# 15P1D_EDA.net
KiCad netlist of a schematic drawn in EasyEDA Pro
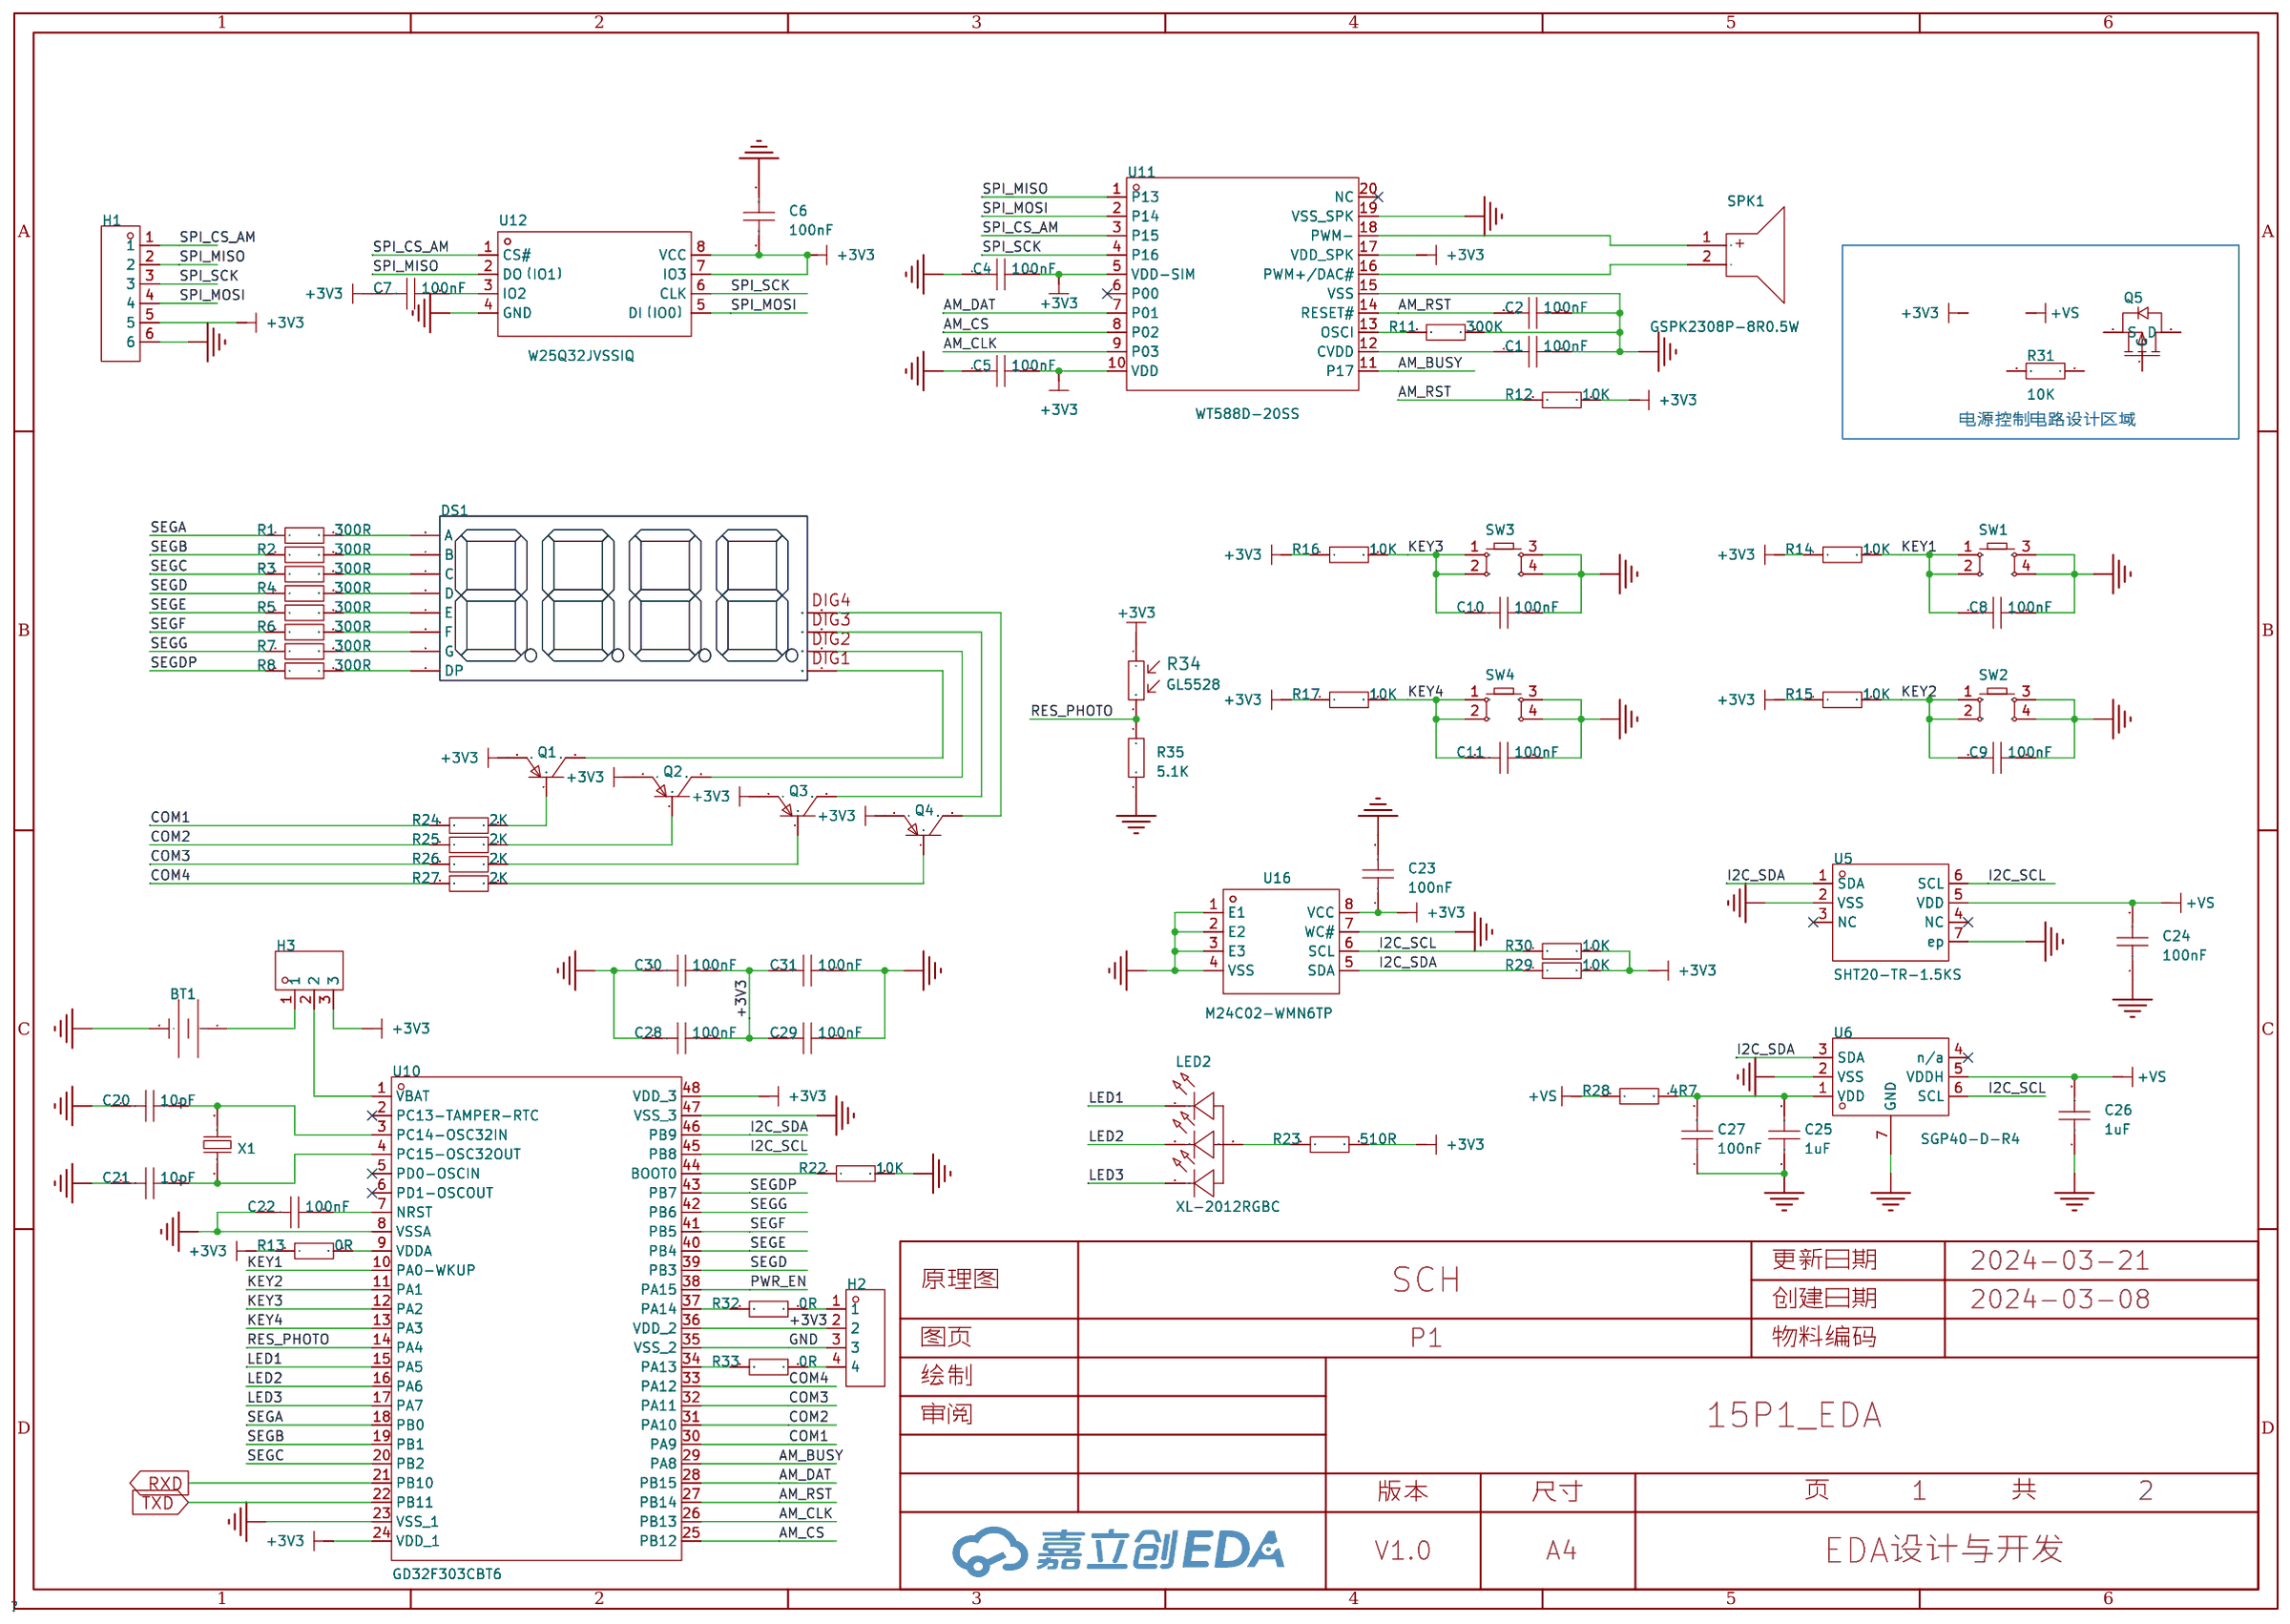
[diagram p0: P1]
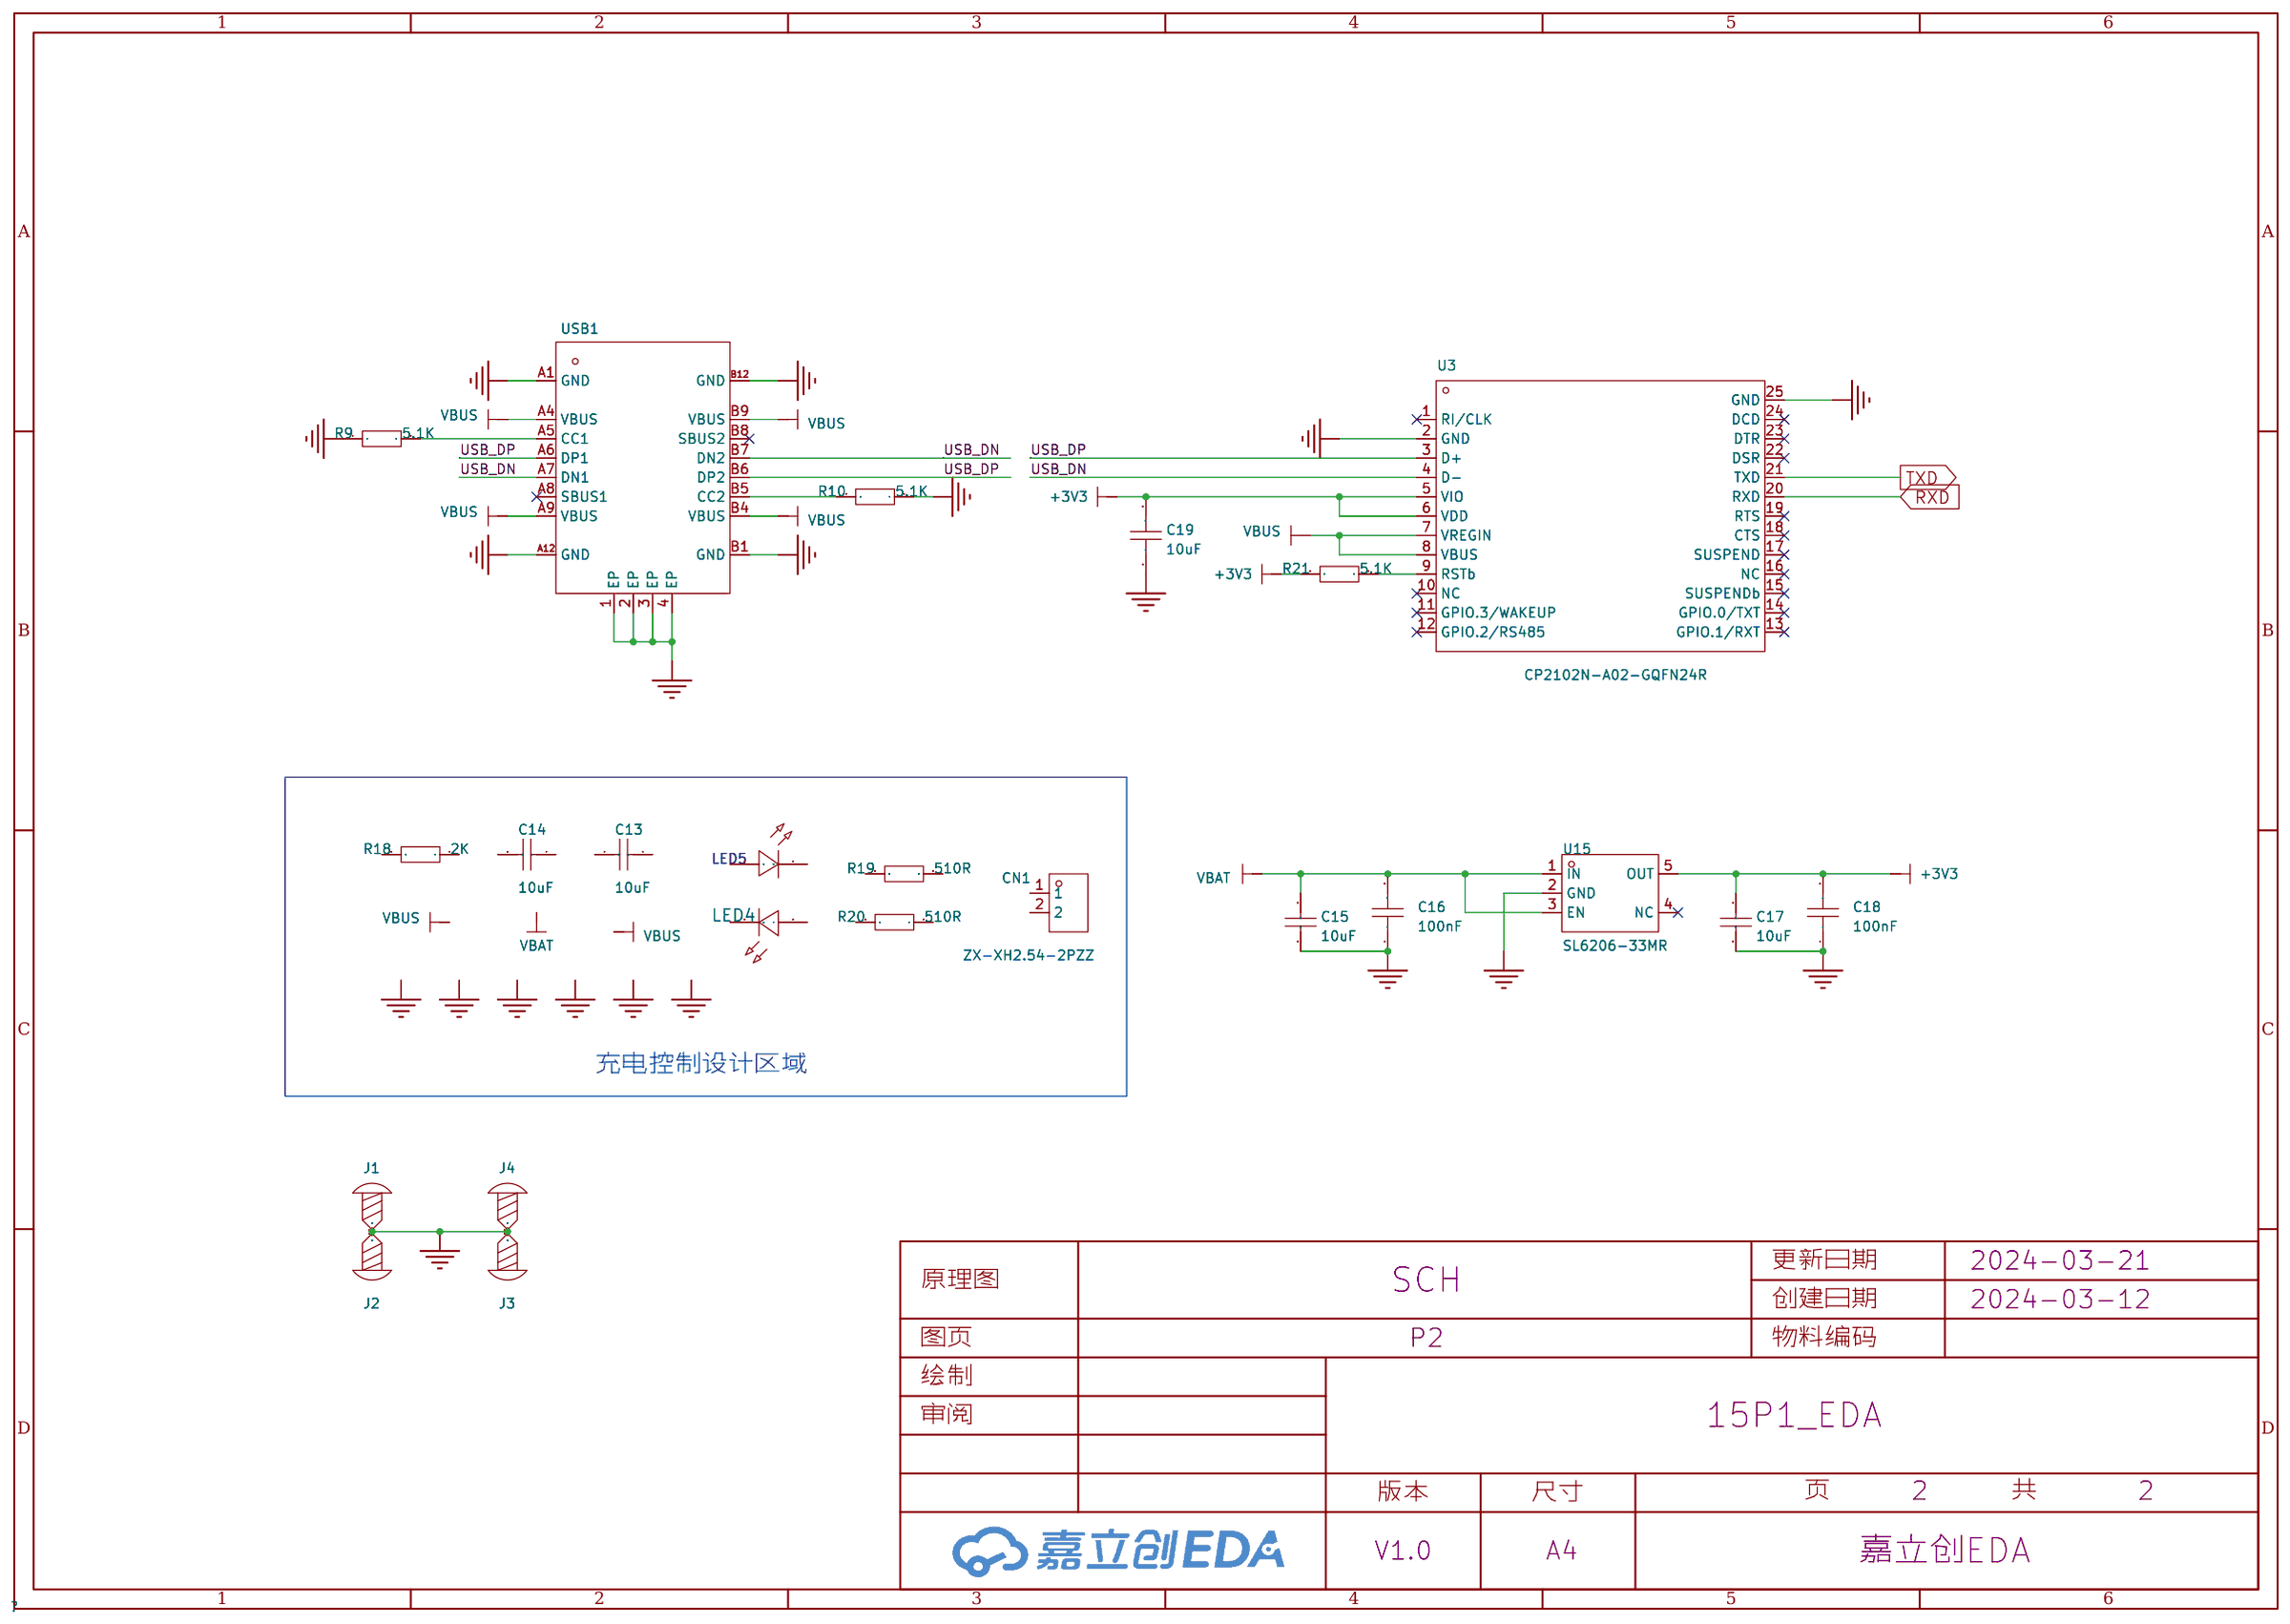
[diagram p1: P2]

(export (version "E")
  (design (tool "Eeschema 10.0.6"))
  (components
    (comp (ref "BT1")
      (value "BS-12-B3AA003")
      (footprint "easyedapro:BAT-SMD_BS-12-B3AA011")
      (description "连接器类型:电池底座;适用电池规格:CR1220;工作温度范围:-25°C~+85°C;")
      (fields (field (name "Manufacturer") "MYOUNG(美阳)"))
      (libsource (lib "easyedapro") (part "BS-12-B3AA003"))
    )
    (comp (ref "C1")
      (value "100nF")
      (footprint "easyedapro:C0805")
      (libsource (lib "easyedapro") (part "CapAcitance"))
    )
    (comp (ref "C2")
      (value "100nF")
      (footprint "easyedapro:C0805")
      (libsource (lib "easyedapro") (part "CapAcitance"))
    )
    (comp (ref "C4")
      (value "100nF")
      (footprint "easyedapro:C0805")
      (libsource (lib "easyedapro") (part "CapAcitance"))
    )
    (comp (ref "C5")
      (value "100nF")
      (footprint "easyedapro:C0805")
      (libsource (lib "easyedapro") (part "CapAcitance"))
    )
    (comp (ref "C6")
      (value "100nF")
      (footprint "easyedapro:C0805")
      (libsource (lib "easyedapro") (part "CapAcitance"))
    )
    (comp (ref "C7")
      (value "100nF")
      (footprint "easyedapro:C0805")
      (libsource (lib "easyedapro") (part "CapAcitance"))
    )
    (comp (ref "C8")
      (value "100nF")
      (footprint "easyedapro:C0805")
      (libsource (lib "easyedapro") (part "CapAcitance"))
    )
    (comp (ref "C9")
      (value "100nF")
      (footprint "easyedapro:C0805")
      (libsource (lib "easyedapro") (part "CapAcitance"))
    )
    (comp (ref "C10")
      (value "100nF")
      (footprint "easyedapro:C0805")
      (libsource (lib "easyedapro") (part "CapAcitance"))
    )
    (comp (ref "C11")
      (value "100nF")
      (footprint "easyedapro:C0805")
      (libsource (lib "easyedapro") (part "CapAcitance"))
    )
    (comp (ref "C20")
      (value "10pF")
      (footprint "easyedapro:C0805")
      (libsource (lib "easyedapro") (part "CapAcitance"))
    )
    (comp (ref "C21")
      (value "10pF")
      (footprint "easyedapro:C0805")
      (libsource (lib "easyedapro") (part "CapAcitance"))
    )
    (comp (ref "C22")
      (value "100nF")
      (footprint "easyedapro:C0805")
      (libsource (lib "easyedapro") (part "CapAcitance"))
    )
    (comp (ref "C23")
      (value "100nF")
      (footprint "easyedapro:C0805")
      (libsource (lib "easyedapro") (part "CapAcitance"))
    )
    (comp (ref "C24")
      (value "100nF")
      (footprint "easyedapro:C0805")
      (libsource (lib "easyedapro") (part "CapAcitance"))
    )
    (comp (ref "C25")
      (value "1uF")
      (footprint "easyedapro:C0805")
      (libsource (lib "easyedapro") (part "CapAcitance"))
    )
    (comp (ref "C26")
      (value "1uF")
      (footprint "easyedapro:C0805")
      (libsource (lib "easyedapro") (part "CapAcitance"))
    )
    (comp (ref "C27")
      (value "100nF")
      (footprint "easyedapro:C0805")
      (libsource (lib "easyedapro") (part "CapAcitance"))
    )
    (comp (ref "C28")
      (value "100nF")
      (footprint "easyedapro:C0805")
      (libsource (lib "easyedapro") (part "CapAcitance"))
    )
    (comp (ref "C29")
      (value "100nF")
      (footprint "easyedapro:C0805")
      (libsource (lib "easyedapro") (part "CapAcitance"))
    )
    (comp (ref "C30")
      (value "100nF")
      (footprint "easyedapro:C0805")
      (libsource (lib "easyedapro") (part "CapAcitance"))
    )
    (comp (ref "C31")
      (value "100nF")
      (footprint "easyedapro:C0805")
      (libsource (lib "easyedapro") (part "CapAcitance"))
    )
    (comp (ref "DS1")
      (value "~")
      (footprint "easyedapro:LED-SEG-TH_FJ5461AH")
      (libsource (lib "easyedapro") (part "LED_SEG_TH_0.56x4"))
    )
    (comp (ref "H1")
      (value "~")
      (footprint "easyedapro:HDR-TH_6P-P2.54-V-F")
      (libsource (lib "easyedapro") (part "Header-Female-2.54_1x6"))
    )
    (comp (ref "H2")
      (value "~")
      (footprint "easyedapro:HDR-TH_4P-P2.54-V-F")
      (libsource (lib "easyedapro") (part "2.54-1*4P母"))
    )
    (comp (ref "H3")
      (value "Jumper3")
      (footprint "easyedapro:HDR-TH_3P-P2.54-V-M-A")
      (libsource (lib "easyedapro") (part "JUMPER3"))
    )
    (comp (ref "LED2")
      (value "XL-2012RGBC")
      (footprint "easyedapro:LED-SMD_4P-L2.0-W1.3-BR")
      (fields (field (name "Manufacturer") "XINGLIGHT(成兴光)"))
      (libsource (lib "easyedapro") (part "XL-2012RGBC"))
    )
    (comp (ref "Q1")
      (value "~")
      (footprint "easyedapro:S8550P_SOT")
      (libsource (lib "easyedapro") (part "PNP"))
    )
    (comp (ref "Q2")
      (value "~")
      (footprint "easyedapro:S8550P_SOT")
      (libsource (lib "easyedapro") (part "PNP"))
    )
    (comp (ref "Q3")
      (value "~")
      (footprint "easyedapro:S8550P_SOT")
      (libsource (lib "easyedapro") (part "PNP"))
    )
    (comp (ref "Q4")
      (value "~")
      (footprint "easyedapro:S8550P_SOT")
      (libsource (lib "easyedapro") (part "PNP"))
    )
    (comp (ref "Q5")
      (value "~")
      (footprint "easyedapro:AO3401A_SOT-23-3")
      (libsource (lib "easyedapro") (part "P_MOS"))
    )
    (comp (ref "R1") (value "300R") (footprint "easyedapro:R0805") (libsource (lib "easyedapro") (part "电阻")))
    (comp (ref "R2") (value "300R") (footprint "easyedapro:R0805") (libsource (lib "easyedapro") (part "电阻")))
    (comp (ref "R3") (value "300R") (footprint "easyedapro:R0805") (libsource (lib "easyedapro") (part "电阻")))
    (comp (ref "R4") (value "300R") (footprint "easyedapro:R0805") (libsource (lib "easyedapro") (part "电阻")))
    (comp (ref "R5") (value "300R") (footprint "easyedapro:R0805") (libsource (lib "easyedapro") (part "电阻")))
    (comp (ref "R6") (value "300R") (footprint "easyedapro:R0805") (libsource (lib "easyedapro") (part "电阻")))
    (comp (ref "R7") (value "300R") (footprint "easyedapro:R0805") (libsource (lib "easyedapro") (part "电阻")))
    (comp (ref "R8") (value "300R") (footprint "easyedapro:R0805") (libsource (lib "easyedapro") (part "电阻")))
    (comp (ref "R11")
      (value "300K")
      (footprint "easyedapro:R0805")
      (libsource (lib "easyedapro") (part "电阻"))
    )
    (comp (ref "R12") (value "10K") (footprint "easyedapro:R0805") (libsource (lib "easyedapro") (part "电阻")))
    (comp (ref "R13") (value "0R") (footprint "easyedapro:R0805") (libsource (lib "easyedapro") (part "电阻")))
    (comp (ref "R14") (value "10K") (footprint "easyedapro:R0805") (libsource (lib "easyedapro") (part "电阻")))
    (comp (ref "R15") (value "10K") (footprint "easyedapro:R0805") (libsource (lib "easyedapro") (part "电阻")))
    (comp (ref "R16") (value "10K") (footprint "easyedapro:R0805") (libsource (lib "easyedapro") (part "电阻")))
    (comp (ref "R17") (value "10K") (footprint "easyedapro:R0805") (libsource (lib "easyedapro") (part "电阻")))
    (comp (ref "R22") (value "10K") (footprint "easyedapro:R0805") (libsource (lib "easyedapro") (part "电阻")))
    (comp (ref "R23")
      (value "510R")
      (footprint "easyedapro:R0805")
      (libsource (lib "easyedapro") (part "电阻"))
    )
    (comp (ref "R24") (value "2K") (footprint "easyedapro:R0805") (libsource (lib "easyedapro") (part "电阻")))
    (comp (ref "R25") (value "2K") (footprint "easyedapro:R0805") (libsource (lib "easyedapro") (part "电阻")))
    (comp (ref "R26") (value "2K") (footprint "easyedapro:R0805") (libsource (lib "easyedapro") (part "电阻")))
    (comp (ref "R27") (value "2K") (footprint "easyedapro:R0805") (libsource (lib "easyedapro") (part "电阻")))
    (comp (ref "R28") (value "4R7") (footprint "easyedapro:R0805") (libsource (lib "easyedapro") (part "电阻")))
    (comp (ref "R29") (value "10K") (footprint "easyedapro:R0805") (libsource (lib "easyedapro") (part "电阻")))
    (comp (ref "R30") (value "10K") (footprint "easyedapro:R0805") (libsource (lib "easyedapro") (part "电阻")))
    (comp (ref "R31") (value "10K") (footprint "easyedapro:R0805") (libsource (lib "easyedapro") (part "电阻")))
    (comp (ref "R32") (value "0R") (footprint "easyedapro:R0805") (libsource (lib "easyedapro") (part "电阻")))
    (comp (ref "R33") (value "0R") (footprint "easyedapro:R0805") (libsource (lib "easyedapro") (part "电阻")))
    (comp (ref "R34")
      (value "GL5528")
      (footprint "easyedapro:RES-TH_L5.1-W4.3-P3.40-D0.5")
      (description "暗电阻:1MΩ;亮电阻 @ 10Lux:8kΩ~20kΩ;光谱峰值(波长):540nm;")
      (fields (field (name "Manufacturer") "森霸"))
      (libsource (lib "easyedapro") (part "GL5528"))
    )
    (comp (ref "R35")
      (value "5.1K")
      (footprint "easyedapro:R0805")
      (libsource (lib "easyedapro") (part "电阻"))
    )
    (comp (ref "SPK1")
      (value "GSPK2308P-8R0.5W")
      (footprint "easyedapro:SPK-TH_BD23.0-P10.00-D0.8-L-RD")
      (fields (field (name "Manufacturer") "INGHAi(赢海)"))
      (libsource (lib "easyedapro") (part "GSPK2308P-8R0.5W"))
    )
    (comp (ref "SW1")
      (value "~")
      (footprint "easyedapro:Key_SMD_12x12x7.3")
      (libsource (lib "easyedapro") (part "轻触按键"))
    )
    (comp (ref "SW2")
      (value "~")
      (footprint "easyedapro:Key_SMD_12x12x7.3")
      (libsource (lib "easyedapro") (part "轻触按键"))
    )
    (comp (ref "SW3")
      (value "~")
      (footprint "easyedapro:Key_SMD_12x12x7.3")
      (libsource (lib "easyedapro") (part "轻触按键"))
    )
    (comp (ref "SW4")
      (value "~")
      (footprint "easyedapro:Key_SMD_12x12x7.3")
      (libsource (lib "easyedapro") (part "轻触按键"))
    )
    (comp (ref "U5")
      (value "SHT20-TR-1.5KS")
      (footprint "easyedapro:DFN-6_L3.0-W3.0-P0.95-TR-EP")
      (description "接口类型:I2C;")
      (fields (field (name "Manufacturer") "Sensirion(瑞士盛思锐)"))
      (libsource (lib "easyedapro") (part "SHT20"))
    )
    (comp (ref "U6")
      (value "SGP40-D-R4")
      (footprint "easyedapro:DFN-6_L2.4-W2.4-P0.80-TL-EP")
      (description "气体类型:空气质量;精度:-;")
      (fields (field (name "Manufacturer") "Sensirion(瑞士盛思锐)"))
      (libsource (lib "easyedapro") (part "SGP40-D-R4"))
    )
    (comp (ref "U10")
      (value "GD32F303CBT6")
      (footprint "easyedapro:LQFP-48_L7.0-W7.0-P0.50-LS9.0-BL")
      (description "CPU内核:CM4;程序存储容量:128KB;RAM总容量:32KB;GPIO端口数量:37;工作电压范围:-;CPU最大主频:120MHz;程序存储器类型:FLASH;")
      (fields (field (name "Manufacturer") "GigaDevice(兆易创新)"))
      (libsource (lib "easyedapro") (part "GD32F303CBT6"))
    )
    (comp (ref "U11")
      (value "WT588D-20SS")
      (footprint "easyedapro:SSOP-20_L7.2-W5.3-P0.65-LS7.8-BL")
      (description "高品质语音芯片")
      (fields (field (name "Manufacturer") "WT(唯创知音)"))
      (libsource (lib "easyedapro") (part "WT588D"))
    )
    (comp (ref "U12")
      (value "W25Q32JVSSIQ")
      (footprint "easyedapro:SOIC-8_L5.3-W5.3-P1.27-LS8.0-BL")
      (description "接口类型:SPI;存储容量:32Mbit;")
      (fields (field (name "Manufacturer") "WINBOND(华邦)"))
      (libsource (lib "easyedapro") (part "W25Q32JVSSIQ"))
    )
    (comp (ref "U16")
      (value "M24C02-WMN6TP")
      (footprint "easyedapro:SOIC-8_L4.9-W3.9-P1.27-LS6.0-BL")
      (description "接口类型:I2C;存储容量:2Kbit;")
      (fields (field (name "Manufacturer") "ST(意法半导体)"))
      (libsource (lib "easyedapro") (part "M24C02-WMN6TP"))
    )
    (comp (ref "X1")
      (value "32.768kHz")
      (footprint "easyedapro:FC-135R_L3.2-W1.5")
      (description "晶振类型:贴片晶振;频率:32.768kHz;常温频差:±20ppm;外接负载电容:12.5pF;")
      (fields (field (name "Manufacturer Part") "Q13FC13500004") (field (name "Manufacturer") "EPSON(爱普生)"))
      (libsource (lib "easyedapro") (part "Q13FC1350000400"))
    )
    (comp (ref "C13")
      (value "10uF")
      (footprint "easyedapro:C1206")
      (description "容值:10uF;精度:±10%;额定电压:50V;材质(温度系数):X5R;")
      (fields
        (field (name "Manufacturer Part") "CL31A106KBHNNNE")
        (field (name "Manufacturer") "SAMSUNG(三星)")
      )
      (libsource (lib "easyedapro") (part "CL31A106KBHNNNE"))
    )
    (comp (ref "C14")
      (value "10uF")
      (footprint "easyedapro:C1206")
      (description "容值:10uF;精度:±10%;额定电压:50V;材质(温度系数):X5R;")
      (fields
        (field (name "Manufacturer Part") "CL31A106KBHNNNE")
        (field (name "Manufacturer") "SAMSUNG(三星)")
      )
      (libsource (lib "easyedapro") (part "CL31A106KBHNNNE"))
    )
    (comp (ref "C15")
      (value "10uF")
      (footprint "easyedapro:C1206")
      (description "容值:10uF;精度:±10%;额定电压:50V;材质(温度系数):X5R;")
      (fields
        (field (name "Manufacturer Part") "CL31A106KBHNNNE")
        (field (name "Manufacturer") "SAMSUNG(三星)")
      )
      (libsource (lib "easyedapro") (part "CL31A106KBHNNNE"))
    )
    (comp (ref "C16")
      (value "100nF")
      (footprint "easyedapro:C0805")
      (libsource (lib "easyedapro") (part "CapAcitance"))
    )
    (comp (ref "C17")
      (value "10uF")
      (footprint "easyedapro:C1206")
      (description "容值:10uF;精度:±10%;额定电压:50V;材质(温度系数):X5R;")
      (fields
        (field (name "Manufacturer Part") "CL31A106KBHNNNE")
        (field (name "Manufacturer") "SAMSUNG(三星)")
      )
      (libsource (lib "easyedapro") (part "CL31A106KBHNNNE"))
    )
    (comp (ref "C18")
      (value "100nF")
      (footprint "easyedapro:C0805")
      (libsource (lib "easyedapro") (part "CapAcitance"))
    )
    (comp (ref "C19")
      (value "10uF")
      (footprint "easyedapro:C0805")
      (libsource (lib "easyedapro") (part "CapAcitance"))
    )
    (comp (ref "CN1")
      (value "ZX-XH2.54-2PZZ")
      (footprint "easyedapro:CONN-TH_2P-P2.50_HX25003-2A")
      (fields (field (name "Manufacturer") "Megastar(兆星)"))
      (libsource (lib "easyedapro") (part "ZX-XH2.54-2PZZ"))
    )
    (comp (ref "J1") (value "~") (footprint "easyedapro:M2螺丝") (libsource (lib "easyedapro") (part "螺丝孔")))
    (comp (ref "J2") (value "~") (footprint "easyedapro:M2螺丝") (libsource (lib "easyedapro") (part "螺丝孔")))
    (comp (ref "J3") (value "~") (footprint "easyedapro:M2螺丝") (libsource (lib "easyedapro") (part "螺丝孔")))
    (comp (ref "J4") (value "~") (footprint "easyedapro:M2螺丝") (libsource (lib "easyedapro") (part "螺丝孔")))
    (comp (ref "LED4")
      (value "~")
      (footprint "easyedapro:LED_0805")
      (libsource (lib "easyedapro") (part "LED_R"))
    )
    (comp (ref "LED5")
      (value "~")
      (footprint "easyedapro:LED_0805")
      (libsource (lib "easyedapro") (part "LED_G"))
    )
    (comp (ref "R9") (value "5.1K") (footprint "easyedapro:R0805") (libsource (lib "easyedapro") (part "电阻")))
    (comp (ref "R10")
      (value "5.1K")
      (footprint "easyedapro:R0805")
      (libsource (lib "easyedapro") (part "电阻"))
    )
    (comp (ref "R18") (value "2K") (footprint "easyedapro:R0805") (libsource (lib "easyedapro") (part "电阻")))
    (comp (ref "R19")
      (value "510R")
      (footprint "easyedapro:R0805")
      (libsource (lib "easyedapro") (part "电阻"))
    )
    (comp (ref "R20")
      (value "510R")
      (footprint "easyedapro:R0805")
      (libsource (lib "easyedapro") (part "电阻"))
    )
    (comp (ref "R21")
      (value "5.1K")
      (footprint "easyedapro:R0805")
      (libsource (lib "easyedapro") (part "电阻"))
    )
    (comp (ref "U3")
      (value "CP2102N-A02-GQFN24R")
      (footprint "easyedapro:QFN-24_L4.0-W4.0-P0.50-TL-EP2.6")
      (description "应用功能:USB转UART;接口协议:UART;")
      (fields (field (name "Manufacturer") "SKYWORKS/SILICON LABS(芯科)"))
      (libsource (lib "easyedapro") (part "CP2102N-A02-GQFN24R"))
    )
    (comp (ref "U15")
      (value "SL6206-33MR")
      (footprint "easyedapro:SOT-23-5_L2.9-W1.6-P0.95-LS2.8-BL")
      (description "输出类型:-;")
      (fields (field (name "Manufacturer") "Slkor(萨科微)"))
      (libsource (lib "easyedapro") (part "SL6206-33MR"))
    )
    (comp (ref "USB1")
      (value "~")
      (footprint "easyedapro:USB_TYPE-C-16P")
      (libsource (lib "easyedapro") (part "USB_TYPE-C-16P"))
    )
  )
  (nets
    (net (code "1") (name "+3V3") (class "Default")
      (node (ref "C17") (pin "2") (pinfunction "2_2") (pintype "input"))
      (node (ref "C18") (pin "2") (pinfunction "2_2") (pintype "input"))
      (node (ref "C19") (pin "2") (pinfunction "2_2") (pintype "input"))
      (node (ref "C23") (pin "1") (pinfunction "1_1") (pintype "input"))
      (node (ref "C28") (pin "1") (pinfunction "1_1") (pintype "input"))
      (node (ref "C29") (pin "2") (pinfunction "2_2") (pintype "input"))
      (node (ref "C30") (pin "1") (pinfunction "1_1") (pintype "input"))
      (node (ref "C31") (pin "2") (pinfunction "2_2") (pintype "input"))
      (node (ref "C4") (pin "2") (pinfunction "2_2") (pintype "input"))
      (node (ref "C5") (pin "2") (pinfunction "2_2") (pintype "input"))
      (node (ref "C6") (pin "2") (pinfunction "2_2") (pintype "input"))
      (node (ref "C7") (pin "1") (pinfunction "1_1") (pintype "input"))
      (node (ref "H1") (pin "5") (pinfunction "5_5") (pintype "unspecified"))
      (node (ref "H2") (pin "2") (pinfunction "2_2") (pintype "unspecified"))
      (node (ref "H3") (pin "3") (pinfunction "3_3") (pintype "input"))
      (node (ref "Q1") (pin "2") (pinfunction "E_2") (pintype "input"))
      (node (ref "Q2") (pin "2") (pinfunction "E_2") (pintype "input"))
      (node (ref "Q3") (pin "2") (pinfunction "E_2") (pintype "input"))
      (node (ref "Q4") (pin "2") (pinfunction "E_2") (pintype "input"))
      (node (ref "R12") (pin "2") (pinfunction "2_2") (pintype "input"))
      (node (ref "R13") (pin "1") (pinfunction "1_1") (pintype "input"))
      (node (ref "R14") (pin "1") (pinfunction "1_1") (pintype "input"))
      (node (ref "R15") (pin "1") (pinfunction "1_1") (pintype "input"))
      (node (ref "R16") (pin "1") (pinfunction "1_1") (pintype "input"))
      (node (ref "R17") (pin "1") (pinfunction "1_1") (pintype "input"))
      (node (ref "R21") (pin "2") (pinfunction "2_2") (pintype "input"))
      (node (ref "R23") (pin "2") (pinfunction "2_2") (pintype "input"))
      (node (ref "R29") (pin "2") (pinfunction "2_2") (pintype "input"))
      (node (ref "R30") (pin "2") (pinfunction "2_2") (pintype "input"))
      (node (ref "R34") (pin "1") (pinfunction "1_1") (pintype "input"))
      (node (ref "U10") (pin "24") (pinfunction "VDD_1_24") (pintype "unspecified"))
      (node (ref "U10") (pin "36") (pinfunction "VDD_2_36") (pintype "unspecified"))
      (node (ref "U10") (pin "48") (pinfunction "VDD_3_48") (pintype "unspecified"))
      (node (ref "U11") (pin "10") (pinfunction "VDD_10") (pintype "input"))
      (node (ref "U11") (pin "17") (pinfunction "VDD_SPK_17") (pintype "input"))
      (node (ref "U11") (pin "5") (pinfunction "VDD-SIM_5") (pintype "input"))
      (node (ref "U12") (pin "7") (pinfunction "IO3_7") (pintype "unspecified"))
      (node (ref "U12") (pin "8") (pinfunction "VCC_8") (pintype "unspecified"))
      (node (ref "U15") (pin "5") (pinfunction "OUT_5") (pintype "unspecified"))
      (node (ref "U16") (pin "8") (pinfunction "VCC_8") (pintype "unspecified"))
      (node (ref "U3") (pin "5") (pinfunction "VIO_5") (pintype "unspecified"))
      (node (ref "U3") (pin "6") (pinfunction "VDD_6") (pintype "unspecified"))
    )
    (net (code "2") (name "+VS") (class "Default")
      (node (ref "C24") (pin "2") (pinfunction "2_2") (pintype "input"))
      (node (ref "C26") (pin "2") (pinfunction "2_2") (pintype "input"))
      (node (ref "R28") (pin "1") (pinfunction "1_1") (pintype "input"))
      (node (ref "U5") (pin "5") (pinfunction "VDD_5") (pintype "unspecified"))
      (node (ref "U6") (pin "5") (pinfunction "VDDH_5") (pintype "unspecified"))
    )
    (net (code "3") (name "AM_BUSY") (class "Default")
      (node (ref "U10") (pin "29") (pinfunction "PA8_29") (pintype "unspecified"))
      (node (ref "U11") (pin "11") (pinfunction "P17_11") (pintype "input"))
    )
    (net (code "4") (name "AM_CLK") (class "Default")
      (node (ref "U10") (pin "26") (pinfunction "PB13_26") (pintype "unspecified"))
      (node (ref "U11") (pin "9") (pinfunction "P03_9") (pintype "input"))
    )
    (net (code "5") (name "AM_CS") (class "Default")
      (node (ref "U10") (pin "25") (pinfunction "PB12_25") (pintype "unspecified"))
      (node (ref "U11") (pin "8") (pinfunction "P02_8") (pintype "input"))
    )
    (net (code "6") (name "AM_DAT") (class "Default")
      (node (ref "U10") (pin "28") (pinfunction "PB15_28") (pintype "unspecified"))
      (node (ref "U11") (pin "7") (pinfunction "P01_7") (pintype "input"))
    )
    (net (code "7") (name "AM_RST") (class "Default")
      (node (ref "C2") (pin "1") (pinfunction "1_1") (pintype "input"))
      (node (ref "R12") (pin "1") (pinfunction "1_1") (pintype "input"))
      (node (ref "U10") (pin "27") (pinfunction "PB14_27") (pintype "unspecified"))
      (node (ref "U11") (pin "14") (pinfunction "RESET#_14") (pintype "input"))
    )
    (net (code "8") (name "COM1") (class "Default")
      (node (ref "R24") (pin "1") (pinfunction "1_1") (pintype "input"))
      (node (ref "U10") (pin "30") (pinfunction "PA9_30") (pintype "unspecified"))
    )
    (net (code "9") (name "COM2") (class "Default")
      (node (ref "R25") (pin "1") (pinfunction "1_1") (pintype "input"))
      (node (ref "U10") (pin "31") (pinfunction "PA10_31") (pintype "unspecified"))
    )
    (net (code "10") (name "COM3") (class "Default")
      (node (ref "R26") (pin "1") (pinfunction "1_1") (pintype "input"))
      (node (ref "U10") (pin "32") (pinfunction "PA11_32") (pintype "unspecified"))
    )
    (net (code "11") (name "COM4") (class "Default")
      (node (ref "R27") (pin "1") (pinfunction "1_1") (pintype "input"))
      (node (ref "U10") (pin "33") (pinfunction "PA12_33") (pintype "unspecified"))
    )
    (net (code "12") (name "GND") (class "Default")
      (node (ref "BT1") (pin "2") (pinfunction "-_2") (pintype "unspecified"))
      (node (ref "C1") (pin "2") (pinfunction "2_2") (pintype "input"))
      (node (ref "C10") (pin "2") (pinfunction "2_2") (pintype "input"))
      (node (ref "C11") (pin "2") (pinfunction "2_2") (pintype "input"))
      (node (ref "C15") (pin "1") (pinfunction "1_1") (pintype "input"))
      (node (ref "C16") (pin "1") (pinfunction "1_1") (pintype "input"))
      (node (ref "C17") (pin "1") (pinfunction "1_1") (pintype "input"))
      (node (ref "C18") (pin "1") (pinfunction "1_1") (pintype "input"))
      (node (ref "C19") (pin "1") (pinfunction "1_1") (pintype "input"))
      (node (ref "C2") (pin "2") (pinfunction "2_2") (pintype "input"))
      (node (ref "C20") (pin "1") (pinfunction "1_1") (pintype "input"))
      (node (ref "C21") (pin "1") (pinfunction "1_1") (pintype "input"))
      (node (ref "C22") (pin "1") (pinfunction "1_1") (pintype "input"))
      (node (ref "C23") (pin "2") (pinfunction "2_2") (pintype "input"))
      (node (ref "C24") (pin "1") (pinfunction "1_1") (pintype "input"))
      (node (ref "C25") (pin "1") (pinfunction "1_1") (pintype "input"))
      (node (ref "C26") (pin "1") (pinfunction "1_1") (pintype "input"))
      (node (ref "C27") (pin "1") (pinfunction "1_1") (pintype "input"))
      (node (ref "C28") (pin "2") (pinfunction "2_2") (pintype "input"))
      (node (ref "C29") (pin "1") (pinfunction "1_1") (pintype "input"))
      (node (ref "C30") (pin "2") (pinfunction "2_2") (pintype "input"))
      (node (ref "C31") (pin "1") (pinfunction "1_1") (pintype "input"))
      (node (ref "C4") (pin "1") (pinfunction "1_1") (pintype "input"))
      (node (ref "C5") (pin "1") (pinfunction "1_1") (pintype "input"))
      (node (ref "C6") (pin "1") (pinfunction "1_1") (pintype "input"))
      (node (ref "C8") (pin "2") (pinfunction "2_2") (pintype "input"))
      (node (ref "C9") (pin "2") (pinfunction "2_2") (pintype "input"))
      (node (ref "H1") (pin "6") (pinfunction "6_6") (pintype "unspecified"))
      (node (ref "H2") (pin "3") (pinfunction "3_3") (pintype "unspecified"))
      (node (ref "J1") (pin "1") (pinfunction "1_1") (pintype "input"))
      (node (ref "J2") (pin "1") (pinfunction "1_1") (pintype "input"))
      (node (ref "J3") (pin "1") (pinfunction "1_1") (pintype "input"))
      (node (ref "J4") (pin "1") (pinfunction "1_1") (pintype "input"))
      (node (ref "R10") (pin "1") (pinfunction "1_1") (pintype "input"))
      (node (ref "R11") (pin "2") (pinfunction "2_2") (pintype "input"))
      (node (ref "R22") (pin "2") (pinfunction "2_2") (pintype "input"))
      (node (ref "R35") (pin "2") (pinfunction "2_2") (pintype "input"))
      (node (ref "R9") (pin "1") (pinfunction "1_1") (pintype "input"))
      (node (ref "SW1") (pin "3") (pinfunction "3_3") (pintype "input"))
      (node (ref "SW1") (pin "4") (pinfunction "4_4") (pintype "input"))
      (node (ref "SW2") (pin "3") (pinfunction "3_3") (pintype "input"))
      (node (ref "SW2") (pin "4") (pinfunction "4_4") (pintype "input"))
      (node (ref "SW3") (pin "3") (pinfunction "3_3") (pintype "input"))
      (node (ref "SW3") (pin "4") (pinfunction "4_4") (pintype "input"))
      (node (ref "SW4") (pin "3") (pinfunction "3_3") (pintype "input"))
      (node (ref "SW4") (pin "4") (pinfunction "4_4") (pintype "input"))
      (node (ref "U10") (pin "23") (pinfunction "VSS_1_23") (pintype "unspecified"))
      (node (ref "U10") (pin "35") (pinfunction "VSS_2_35") (pintype "unspecified"))
      (node (ref "U10") (pin "47") (pinfunction "VSS_3_47") (pintype "unspecified"))
      (node (ref "U10") (pin "8") (pinfunction "VSSA_8") (pintype "unspecified"))
      (node (ref "U11") (pin "15") (pinfunction "VSS_15") (pintype "input"))
      (node (ref "U11") (pin "19") (pinfunction "VSS_SPK_19") (pintype "input"))
      (node (ref "U12") (pin "4") (pinfunction "GND_4") (pintype "unspecified"))
      (node (ref "U15") (pin "2") (pinfunction "GND_2") (pintype "unspecified"))
      (node (ref "U16") (pin "1") (pinfunction "E1_1") (pintype "unspecified"))
      (node (ref "U16") (pin "2") (pinfunction "E2_2") (pintype "unspecified"))
      (node (ref "U16") (pin "3") (pinfunction "E3_3") (pintype "unspecified"))
      (node (ref "U16") (pin "4") (pinfunction "VSS_4") (pintype "unspecified"))
      (node (ref "U16") (pin "7") (pinfunction "WC#_7") (pintype "unspecified"))
      (node (ref "U3") (pin "2") (pinfunction "GND_2") (pintype "unspecified"))
      (node (ref "U3") (pin "25") (pinfunction "GND_25") (pintype "unspecified"))
      (node (ref "U5") (pin "2") (pinfunction "VSS_2") (pintype "unspecified"))
      (node (ref "U5") (pin "7") (pinfunction "ep_7") (pintype "unspecified"))
      (node (ref "U6") (pin "2") (pinfunction "VSS_2") (pintype "unspecified"))
      (node (ref "U6") (pin "7") (pinfunction "GND_7") (pintype "unspecified"))
      (node (ref "USB1") (pin "1") (pinfunction "EP_1") (pintype "input"))
      (node (ref "USB1") (pin "2") (pinfunction "EP_2") (pintype "input"))
      (node (ref "USB1") (pin "3") (pinfunction "EP_3") (pintype "input"))
      (node (ref "USB1") (pin "4") (pinfunction "EP_4") (pintype "input"))
      (node (ref "USB1") (pin "A1") (pinfunction "GND_A1") (pintype "input"))
      (node (ref "USB1") (pin "A12") (pinfunction "GND_A12") (pintype "input"))
      (node (ref "USB1") (pin "B1") (pinfunction "GND_B1") (pintype "input"))
      (node (ref "USB1") (pin "B12") (pinfunction "GND_B12") (pintype "input"))
    )
    (net (code "13") (name "I2C_SCL") (class "Default")
      (node (ref "R30") (pin "1") (pinfunction "1_1") (pintype "input"))
      (node (ref "U10") (pin "45") (pinfunction "PB8_45") (pintype "unspecified"))
      (node (ref "U16") (pin "6") (pinfunction "SCL_6") (pintype "unspecified"))
      (node (ref "U5") (pin "6") (pinfunction "SCL_6") (pintype "unspecified"))
      (node (ref "U6") (pin "6") (pinfunction "SCL_6") (pintype "unspecified"))
    )
    (net (code "14") (name "I2C_SDA") (class "Default")
      (node (ref "R29") (pin "1") (pinfunction "1_1") (pintype "input"))
      (node (ref "U10") (pin "46") (pinfunction "PB9_46") (pintype "unspecified"))
      (node (ref "U16") (pin "5") (pinfunction "SDA_5") (pintype "unspecified"))
      (node (ref "U5") (pin "1") (pinfunction "SDA_1") (pintype "unspecified"))
      (node (ref "U6") (pin "3") (pinfunction "SDA_3") (pintype "unspecified"))
    )
    (net (code "15") (name "KEY1") (class "Default")
      (node (ref "C8") (pin "1") (pinfunction "1_1") (pintype "input"))
      (node (ref "R14") (pin "2") (pinfunction "2_2") (pintype "input"))
      (node (ref "SW1") (pin "1") (pinfunction "1_1") (pintype "input"))
      (node (ref "SW1") (pin "2") (pinfunction "2_2") (pintype "input"))
      (node (ref "U10") (pin "10") (pinfunction "PA0-WKUP_10") (pintype "unspecified"))
    )
    (net (code "16") (name "KEY2") (class "Default")
      (node (ref "C9") (pin "1") (pinfunction "1_1") (pintype "input"))
      (node (ref "R15") (pin "2") (pinfunction "2_2") (pintype "input"))
      (node (ref "SW2") (pin "1") (pinfunction "1_1") (pintype "input"))
      (node (ref "SW2") (pin "2") (pinfunction "2_2") (pintype "input"))
      (node (ref "U10") (pin "11") (pinfunction "PA1_11") (pintype "unspecified"))
    )
    (net (code "17") (name "KEY3") (class "Default")
      (node (ref "C10") (pin "1") (pinfunction "1_1") (pintype "input"))
      (node (ref "R16") (pin "2") (pinfunction "2_2") (pintype "input"))
      (node (ref "SW3") (pin "1") (pinfunction "1_1") (pintype "input"))
      (node (ref "SW3") (pin "2") (pinfunction "2_2") (pintype "input"))
      (node (ref "U10") (pin "12") (pinfunction "PA2_12") (pintype "unspecified"))
    )
    (net (code "18") (name "KEY4") (class "Default")
      (node (ref "C11") (pin "1") (pinfunction "1_1") (pintype "input"))
      (node (ref "R17") (pin "2") (pinfunction "2_2") (pintype "input"))
      (node (ref "SW4") (pin "1") (pinfunction "1_1") (pintype "input"))
      (node (ref "SW4") (pin "2") (pinfunction "2_2") (pintype "input"))
      (node (ref "U10") (pin "13") (pinfunction "PA3_13") (pintype "unspecified"))
    )
    (net (code "19") (name "LED1") (class "Default")
      (node (ref "LED2") (pin "1") (pinfunction "1_1") (pintype "unspecified"))
      (node (ref "U10") (pin "15") (pinfunction "PA5_15") (pintype "unspecified"))
    )
    (net (code "20") (name "LED2") (class "Default")
      (node (ref "LED2") (pin "2") (pinfunction "2_2") (pintype "unspecified"))
      (node (ref "U10") (pin "16") (pinfunction "PA6_16") (pintype "unspecified"))
    )
    (net (code "21") (name "LED3") (class "Default")
      (node (ref "LED2") (pin "4") (pinfunction "4_4") (pintype "unspecified"))
      (node (ref "U10") (pin "17") (pinfunction "PA7_17") (pintype "unspecified"))
    )
    (net (code "22") (name "Net-(BT1-+)") (class "Default")
      (node (ref "BT1") (pin "1") (pinfunction "+_1") (pintype "unspecified"))
      (node (ref "H3") (pin "1") (pinfunction "1_1") (pintype "input"))
    )
    (net (code "23") (name "Net-(DS1-A)") (class "Default")
      (node (ref "DS1") (pin "11") (pinfunction "A_11") (pintype "input"))
      (node (ref "R1") (pin "2") (pinfunction "2_2") (pintype "input"))
    )
    (net (code "24") (name "Net-(DS1-B)") (class "Default")
      (node (ref "DS1") (pin "7") (pinfunction "B_7") (pintype "input"))
      (node (ref "R2") (pin "2") (pinfunction "2_2") (pintype "input"))
    )
    (net (code "25") (name "Net-(DS1-C)") (class "Default")
      (node (ref "DS1") (pin "4") (pinfunction "C_4") (pintype "input"))
      (node (ref "R3") (pin "2") (pinfunction "2_2") (pintype "input"))
    )
    (net (code "26") (name "Net-(DS1-D)") (class "Default")
      (node (ref "DS1") (pin "2") (pinfunction "D_2") (pintype "input"))
      (node (ref "R4") (pin "2") (pinfunction "2_2") (pintype "input"))
    )
    (net (code "27") (name "Net-(DS1-DIG1)") (class "Default")
      (node (ref "DS1") (pin "12") (pinfunction "DIG1_12") (pintype "input"))
      (node (ref "Q1") (pin "3") (pinfunction "C_3") (pintype "input"))
    )
    (net (code "28") (name "Net-(DS1-DIG2)") (class "Default")
      (node (ref "DS1") (pin "9") (pinfunction "DIG2_9") (pintype "input"))
      (node (ref "Q2") (pin "3") (pinfunction "C_3") (pintype "input"))
    )
    (net (code "29") (name "Net-(DS1-DIG3)") (class "Default")
      (node (ref "DS1") (pin "8") (pinfunction "DIG3_8") (pintype "input"))
      (node (ref "Q3") (pin "3") (pinfunction "C_3") (pintype "input"))
    )
    (net (code "30") (name "Net-(DS1-DIG4)") (class "Default")
      (node (ref "DS1") (pin "6") (pinfunction "DIG4_6") (pintype "input"))
      (node (ref "Q4") (pin "3") (pinfunction "C_3") (pintype "input"))
    )
    (net (code "31") (name "Net-(DS1-DP)") (class "Default")
      (node (ref "DS1") (pin "3") (pinfunction "DP_3") (pintype "input"))
      (node (ref "R8") (pin "2") (pinfunction "2_2") (pintype "input"))
    )
    (net (code "32") (name "Net-(DS1-E)") (class "Default")
      (node (ref "DS1") (pin "1") (pinfunction "E_1") (pintype "input"))
      (node (ref "R5") (pin "2") (pinfunction "2_2") (pintype "input"))
    )
    (net (code "33") (name "Net-(DS1-F)") (class "Default")
      (node (ref "DS1") (pin "10") (pinfunction "F_10") (pintype "input"))
      (node (ref "R6") (pin "2") (pinfunction "2_2") (pintype "input"))
    )
    (net (code "34") (name "Net-(DS1-G)") (class "Default")
      (node (ref "DS1") (pin "5") (pinfunction "G_5") (pintype "input"))
      (node (ref "R7") (pin "2") (pinfunction "2_2") (pintype "input"))
    )
    (net (code "35") (name "Net-(H2-Pad1)") (class "Default")
      (node (ref "H2") (pin "1") (pinfunction "1_1") (pintype "unspecified"))
      (node (ref "R32") (pin "2") (pinfunction "2_2") (pintype "input"))
    )
    (net (code "36") (name "Net-(H2-Pad4)") (class "Default")
      (node (ref "H2") (pin "4") (pinfunction "4_4") (pintype "unspecified"))
      (node (ref "R33") (pin "2") (pinfunction "2_2") (pintype "input"))
    )
    (net (code "37") (name "Net-(LED2-Pad3)") (class "Default")
      (node (ref "LED2") (pin "3") (pinfunction "3_3") (pintype "unspecified"))
      (node (ref "R23") (pin "1") (pinfunction "1_1") (pintype "input"))
    )
    (net (code "38") (name "Net-(Q1-B)") (class "Default")
      (node (ref "Q1") (pin "1") (pinfunction "B_1") (pintype "input"))
      (node (ref "R24") (pin "2") (pinfunction "2_2") (pintype "input"))
    )
    (net (code "39") (name "Net-(Q2-B)") (class "Default")
      (node (ref "Q2") (pin "1") (pinfunction "B_1") (pintype "input"))
      (node (ref "R25") (pin "2") (pinfunction "2_2") (pintype "input"))
    )
    (net (code "40") (name "Net-(Q3-B)") (class "Default")
      (node (ref "Q3") (pin "1") (pinfunction "B_1") (pintype "input"))
      (node (ref "R26") (pin "2") (pinfunction "2_2") (pintype "input"))
    )
    (net (code "41") (name "Net-(Q4-B)") (class "Default")
      (node (ref "Q4") (pin "1") (pinfunction "B_1") (pintype "input"))
      (node (ref "R27") (pin "2") (pinfunction "2_2") (pintype "input"))
    )
    (net (code "42") (name "Net-(SPK1-+)") (class "Default")
      (node (ref "SPK1") (pin "1") (pinfunction "+_1") (pintype "input"))
      (node (ref "U11") (pin "18") (pinfunction "PWM-_18") (pintype "input"))
    )
    (net (code "43") (name "Net-(SPK1--)") (class "Default")
      (node (ref "SPK1") (pin "2") (pinfunction "-_2") (pintype "input"))
      (node (ref "U11") (pin "16") (pinfunction "PWM+/DAC#_16") (pintype "input"))
    )
    (net (code "44") (name "Net-(U3-RSTb)") (class "Default")
      (node (ref "R21") (pin "1") (pinfunction "1_1") (pintype "input"))
      (node (ref "U3") (pin "9") (pinfunction "RSTb_9") (pintype "unspecified"))
    )
    (net (code "45") (name "Net-(U6-VDD)") (class "Default")
      (node (ref "C25") (pin "2") (pinfunction "2_2") (pintype "input"))
      (node (ref "C27") (pin "2") (pinfunction "2_2") (pintype "input"))
      (node (ref "R28") (pin "2") (pinfunction "2_2") (pintype "input"))
      (node (ref "U6") (pin "1") (pinfunction "VDD_1") (pintype "unspecified"))
    )
    (net (code "46") (name "Net-(U10-BOOT0)") (class "Default")
      (node (ref "R22") (pin "1") (pinfunction "1_1") (pintype "input"))
      (node (ref "U10") (pin "44") (pinfunction "BOOT0_44") (pintype "unspecified"))
    )
    (net (code "47") (name "Net-(U10-NRST)") (class "Default")
      (node (ref "C22") (pin "2") (pinfunction "2_2") (pintype "input"))
      (node (ref "U10") (pin "7") (pinfunction "NRST_7") (pintype "unspecified"))
    )
    (net (code "48") (name "Net-(U10-PA13)") (class "Default")
      (node (ref "R33") (pin "1") (pinfunction "1_1") (pintype "input"))
      (node (ref "U10") (pin "34") (pinfunction "PA13_34") (pintype "unspecified"))
    )
    (net (code "49") (name "Net-(U10-PA14)") (class "Default")
      (node (ref "R32") (pin "1") (pinfunction "1_1") (pintype "input"))
      (node (ref "U10") (pin "37") (pinfunction "PA14_37") (pintype "unspecified"))
    )
    (net (code "50") (name "Net-(U10-PC14-OSC32IN)") (class "Default")
      (node (ref "C20") (pin "2") (pinfunction "2_2") (pintype "input"))
      (node (ref "U10") (pin "3") (pinfunction "PC14-OSC32IN_3") (pintype "unspecified"))
      (node (ref "X1") (pin "1") (pinfunction "1_1") (pintype "unspecified"))
    )
    (net (code "51") (name "Net-(U10-PC15-OSC32OUT)") (class "Default")
      (node (ref "C21") (pin "2") (pinfunction "2_2") (pintype "input"))
      (node (ref "U10") (pin "4") (pinfunction "PC15-OSC32OUT_4") (pintype "unspecified"))
      (node (ref "X1") (pin "2") (pinfunction "2_2") (pintype "unspecified"))
    )
    (net (code "52") (name "Net-(U10-VBAT)") (class "Default")
      (node (ref "H3") (pin "2") (pinfunction "2_2") (pintype "input"))
      (node (ref "U10") (pin "1") (pinfunction "VBAT_1") (pintype "unspecified"))
    )
    (net (code "53") (name "Net-(U10-VDDA)") (class "Default")
      (node (ref "R13") (pin "2") (pinfunction "2_2") (pintype "input"))
      (node (ref "U10") (pin "9") (pinfunction "VDDA_9") (pintype "unspecified"))
    )
    (net (code "54") (name "Net-(U11-CVDD)") (class "Default")
      (node (ref "C1") (pin "1") (pinfunction "1_1") (pintype "input"))
      (node (ref "U11") (pin "12") (pinfunction "CVDD_12") (pintype "input"))
    )
    (net (code "55") (name "Net-(U11-OSCI)") (class "Default")
      (node (ref "R11") (pin "1") (pinfunction "1_1") (pintype "input"))
      (node (ref "U11") (pin "13") (pinfunction "OSCI_13") (pintype "input"))
    )
    (net (code "56") (name "Net-(U12-IO2)") (class "Default")
      (node (ref "C7") (pin "2") (pinfunction "2_2") (pintype "input"))
      (node (ref "U12") (pin "3") (pinfunction "IO2_3") (pintype "unspecified"))
    )
    (net (code "57") (name "Net-(USB1-CC1)") (class "Default")
      (node (ref "R9") (pin "2") (pinfunction "2_2") (pintype "input"))
      (node (ref "USB1") (pin "A5") (pinfunction "CC1_A5") (pintype "input"))
    )
    (net (code "58") (name "Net-(USB1-CC2)") (class "Default")
      (node (ref "R10") (pin "2") (pinfunction "2_2") (pintype "input"))
      (node (ref "USB1") (pin "B5") (pinfunction "CC2_B5") (pintype "input"))
    )
    (net (code "59") (name "PWR_EN") (class "Default")
      (node (ref "U10") (pin "38") (pinfunction "PA15_38") (pintype "unspecified"))
    )
    (net (code "60") (name "RES_PHOTO") (class "Default")
      (node (ref "R34") (pin "2") (pinfunction "2_2") (pintype "input"))
      (node (ref "R35") (pin "1") (pinfunction "1_1") (pintype "input"))
      (node (ref "U10") (pin "14") (pinfunction "PA4_14") (pintype "unspecified"))
    )
    (net (code "61") (name "RXD") (class "Default")
      (node (ref "U10") (pin "21") (pinfunction "PB10_21") (pintype "unspecified"))
      (node (ref "U3") (pin "20") (pinfunction "RXD_20") (pintype "unspecified"))
    )
    (net (code "62") (name "SEGA") (class "Default")
      (node (ref "R1") (pin "1") (pinfunction "1_1") (pintype "input"))
      (node (ref "U10") (pin "18") (pinfunction "PB0_18") (pintype "unspecified"))
    )
    (net (code "63") (name "SEGB") (class "Default")
      (node (ref "R2") (pin "1") (pinfunction "1_1") (pintype "input"))
      (node (ref "U10") (pin "19") (pinfunction "PB1_19") (pintype "unspecified"))
    )
    (net (code "64") (name "SEGC") (class "Default")
      (node (ref "R3") (pin "1") (pinfunction "1_1") (pintype "input"))
      (node (ref "U10") (pin "20") (pinfunction "PB2_20") (pintype "unspecified"))
    )
    (net (code "65") (name "SEGD") (class "Default")
      (node (ref "R4") (pin "1") (pinfunction "1_1") (pintype "input"))
      (node (ref "U10") (pin "39") (pinfunction "PB3_39") (pintype "unspecified"))
    )
    (net (code "66") (name "SEGDP") (class "Default")
      (node (ref "R8") (pin "1") (pinfunction "1_1") (pintype "input"))
      (node (ref "U10") (pin "43") (pinfunction "PB7_43") (pintype "unspecified"))
    )
    (net (code "67") (name "SEGE") (class "Default")
      (node (ref "R5") (pin "1") (pinfunction "1_1") (pintype "input"))
      (node (ref "U10") (pin "40") (pinfunction "PB4_40") (pintype "unspecified"))
    )
    (net (code "68") (name "SEGF") (class "Default")
      (node (ref "R6") (pin "1") (pinfunction "1_1") (pintype "input"))
      (node (ref "U10") (pin "41") (pinfunction "PB5_41") (pintype "unspecified"))
    )
    (net (code "69") (name "SEGG") (class "Default")
      (node (ref "R7") (pin "1") (pinfunction "1_1") (pintype "input"))
      (node (ref "U10") (pin "42") (pinfunction "PB6_42") (pintype "unspecified"))
    )
    (net (code "70") (name "SPI_CS_AM") (class "Default")
      (node (ref "H1") (pin "1") (pinfunction "1_1") (pintype "unspecified"))
      (node (ref "U11") (pin "3") (pinfunction "P15_3") (pintype "input"))
      (node (ref "U12") (pin "1") (pinfunction "CS#_1") (pintype "unspecified"))
    )
    (net (code "71") (name "SPI_MISO") (class "Default")
      (node (ref "H1") (pin "2") (pinfunction "2_2") (pintype "unspecified"))
      (node (ref "U11") (pin "1") (pinfunction "P13_1") (pintype "input"))
      (node (ref "U12") (pin "2") (pinfunction "DO（IO1）_2") (pintype "unspecified"))
    )
    (net (code "72") (name "SPI_MOSI") (class "Default")
      (node (ref "H1") (pin "4") (pinfunction "4_4") (pintype "unspecified"))
      (node (ref "U11") (pin "2") (pinfunction "P14_2") (pintype "input"))
      (node (ref "U12") (pin "5") (pinfunction "DI（IO0）_5") (pintype "unspecified"))
    )
    (net (code "73") (name "SPI_SCK") (class "Default")
      (node (ref "H1") (pin "3") (pinfunction "3_3") (pintype "unspecified"))
      (node (ref "U11") (pin "4") (pinfunction "P16_4") (pintype "input"))
      (node (ref "U12") (pin "6") (pinfunction "CLK_6") (pintype "unspecified"))
    )
    (net (code "74") (name "TXD") (class "Default")
      (node (ref "U10") (pin "22") (pinfunction "PB11_22") (pintype "unspecified"))
      (node (ref "U3") (pin "21") (pinfunction "TXD_21") (pintype "unspecified"))
    )
    (net (code "75") (name "USB_DN") (class "Default")
      (node (ref "U3") (pin "4") (pinfunction "D-_4") (pintype "unspecified"))
      (node (ref "USB1") (pin "A7") (pinfunction "DN1_A7") (pintype "input"))
      (node (ref "USB1") (pin "B7") (pinfunction "DN2_B7") (pintype "input"))
    )
    (net (code "76") (name "USB_DP") (class "Default")
      (node (ref "U3") (pin "3") (pinfunction "D+_3") (pintype "unspecified"))
      (node (ref "USB1") (pin "A6") (pinfunction "DP1_A6") (pintype "input"))
      (node (ref "USB1") (pin "B6") (pinfunction "DP2_B6") (pintype "input"))
    )
    (net (code "77") (name "VBAT") (class "Default")
      (node (ref "C15") (pin "2") (pinfunction "2_2") (pintype "input"))
      (node (ref "C16") (pin "2") (pinfunction "2_2") (pintype "input"))
      (node (ref "U15") (pin "1") (pinfunction "IN_1") (pintype "unspecified"))
      (node (ref "U15") (pin "3") (pinfunction "EN_3") (pintype "unspecified"))
    )
    (net (code "78") (name "VBUS") (class "Default")
      (node (ref "U3") (pin "7") (pinfunction "VREGIN_7") (pintype "unspecified"))
      (node (ref "U3") (pin "8") (pinfunction "VBUS_8") (pintype "unspecified"))
      (node (ref "USB1") (pin "A4") (pinfunction "VBUS_A4") (pintype "input"))
      (node (ref "USB1") (pin "A9") (pinfunction "VBUS_A9") (pintype "input"))
      (node (ref "USB1") (pin "B4") (pinfunction "VBUS_B4") (pintype "input"))
      (node (ref "USB1") (pin "B9") (pinfunction "VBUS_B9") (pintype "input"))
    )
    (net (code "79") (name "unconnected-(C13-Pad1)") (class "Default")
      (node (ref "C13") (pin "1") (pinfunction "1_1") (pintype "input"))
    )
    (net (code "80") (name "unconnected-(C13-Pad2)") (class "Default")
      (node (ref "C13") (pin "2") (pinfunction "2_2") (pintype "input"))
    )
    (net (code "81") (name "unconnected-(C14-Pad1)") (class "Default")
      (node (ref "C14") (pin "1") (pinfunction "1_1") (pintype "input"))
    )
    (net (code "82") (name "unconnected-(C14-Pad2)") (class "Default")
      (node (ref "C14") (pin "2") (pinfunction "2_2") (pintype "input"))
    )
    (net (code "83") (name "unconnected-(CN1-Pad1)") (class "Default")
      (node (ref "CN1") (pin "1") (pinfunction "1_1") (pintype "unspecified"))
    )
    (net (code "84") (name "unconnected-(CN1-Pad2)") (class "Default")
      (node (ref "CN1") (pin "2") (pinfunction "2_2") (pintype "unspecified"))
    )
    (net (code "85") (name "unconnected-(LED4-A-Pad2)") (class "Default")
      (node (ref "LED4") (pin "2") (pinfunction "A_2") (pintype "input"))
    )
    (net (code "86") (name "unconnected-(LED4-C-Pad1)") (class "Default")
      (node (ref "LED4") (pin "1") (pinfunction "C_1") (pintype "input"))
    )
    (net (code "87") (name "unconnected-(LED5-A-Pad2)") (class "Default")
      (node (ref "LED5") (pin "2") (pinfunction "A_2") (pintype "input"))
    )
    (net (code "88") (name "unconnected-(LED5-C-Pad1)") (class "Default")
      (node (ref "LED5") (pin "1") (pinfunction "C_1") (pintype "input"))
    )
    (net (code "89") (name "unconnected-(Q5-D-Pad3)") (class "Default")
      (node (ref "Q5") (pin "3") (pinfunction "D_3") (pintype "input"))
    )
    (net (code "90") (name "unconnected-(Q5-G-Pad1)") (class "Default")
      (node (ref "Q5") (pin "1") (pinfunction "G_1") (pintype "input"))
    )
    (net (code "91") (name "unconnected-(Q5-S-Pad2)") (class "Default")
      (node (ref "Q5") (pin "2") (pinfunction "S_2") (pintype "input"))
    )
    (net (code "92") (name "unconnected-(R18-Pad1)") (class "Default")
      (node (ref "R18") (pin "1") (pinfunction "1_1") (pintype "input"))
    )
    (net (code "93") (name "unconnected-(R18-Pad2)") (class "Default")
      (node (ref "R18") (pin "2") (pinfunction "2_2") (pintype "input"))
    )
    (net (code "94") (name "unconnected-(R19-Pad1)") (class "Default")
      (node (ref "R19") (pin "1") (pinfunction "1_1") (pintype "input"))
    )
    (net (code "95") (name "unconnected-(R19-Pad2)") (class "Default")
      (node (ref "R19") (pin "2") (pinfunction "2_2") (pintype "input"))
    )
    (net (code "96") (name "unconnected-(R20-Pad1)") (class "Default")
      (node (ref "R20") (pin "1") (pinfunction "1_1") (pintype "input"))
    )
    (net (code "97") (name "unconnected-(R20-Pad2)") (class "Default")
      (node (ref "R20") (pin "2") (pinfunction "2_2") (pintype "input"))
    )
    (net (code "98") (name "unconnected-(R31-Pad1)") (class "Default")
      (node (ref "R31") (pin "1") (pinfunction "1_1") (pintype "input"))
    )
    (net (code "99") (name "unconnected-(R31-Pad2)") (class "Default")
      (node (ref "R31") (pin "2") (pinfunction "2_2") (pintype "input"))
    )
    (net (code "100") (name "unconnected-(U3-CTS-Pad18)") (class "Default")
      (node (ref "U3") (pin "18") (pinfunction "CTS_18") (pintype "unspecified+no_connect"))
    )
    (net (code "101") (name "unconnected-(U3-DCD-Pad24)") (class "Default")
      (node (ref "U3") (pin "24") (pinfunction "DCD_24") (pintype "unspecified+no_connect"))
    )
    (net (code "102") (name "unconnected-(U3-DSR-Pad22)") (class "Default")
      (node (ref "U3") (pin "22") (pinfunction "DSR_22") (pintype "unspecified+no_connect"))
    )
    (net (code "103") (name "unconnected-(U3-DTR-Pad23)") (class "Default")
      (node (ref "U3") (pin "23") (pinfunction "DTR_23") (pintype "unspecified+no_connect"))
    )
    (net (code "104") (name "unconnected-(U3-GPIO.0{slash}TXT-Pad14)") (class "Default")
      (node (ref "U3") (pin "14") (pinfunction "GPIO.0/TXT_14") (pintype "unspecified+no_connect"))
    )
    (net (code "105") (name "unconnected-(U3-GPIO.1{slash}RXT-Pad13)") (class "Default")
      (node (ref "U3") (pin "13") (pinfunction "GPIO.1/RXT_13") (pintype "unspecified+no_connect"))
    )
    (net (code "106") (name "unconnected-(U3-GPIO.2{slash}RS485-Pad12)") (class "Default")
      (node (ref "U3") (pin "12") (pinfunction "GPIO.2/RS485_12") (pintype "unspecified+no_connect"))
    )
    (net (code "107") (name "unconnected-(U3-GPIO.3{slash}WAKEUP-Pad11)") (class "Default")
      (node (ref "U3") (pin "11") (pinfunction "GPIO.3/WAKEUP_11") (pintype "unspecified+no_connect"))
    )
    (net (code "108") (name "unconnected-(U3-NC-Pad10)") (class "Default")
      (node (ref "U3") (pin "10") (pinfunction "NC_10") (pintype "unspecified+no_connect"))
    )
    (net (code "109") (name "unconnected-(U3-NC-Pad16)") (class "Default")
      (node (ref "U3") (pin "16") (pinfunction "NC_16") (pintype "unspecified+no_connect"))
    )
    (net (code "110") (name "unconnected-(U3-RI{slash}CLK-Pad1)") (class "Default")
      (node (ref "U3") (pin "1") (pinfunction "RI/CLK_1") (pintype "unspecified+no_connect"))
    )
    (net (code "111") (name "unconnected-(U3-RTS-Pad19)") (class "Default")
      (node (ref "U3") (pin "19") (pinfunction "RTS_19") (pintype "unspecified+no_connect"))
    )
    (net (code "112") (name "unconnected-(U3-SUSPEND-Pad17)") (class "Default")
      (node (ref "U3") (pin "17") (pinfunction "SUSPEND_17") (pintype "unspecified+no_connect"))
    )
    (net (code "113") (name "unconnected-(U3-SUSPENDb-Pad15)") (class "Default")
      (node (ref "U3") (pin "15") (pinfunction "SUSPENDb_15") (pintype "unspecified+no_connect"))
    )
    (net (code "114") (name "unconnected-(U5-NC-Pad3)") (class "Default")
      (node (ref "U5") (pin "3") (pinfunction "NC_3") (pintype "unspecified+no_connect"))
    )
    (net (code "115") (name "unconnected-(U5-NC-Pad4)") (class "Default")
      (node (ref "U5") (pin "4") (pinfunction "NC_4") (pintype "unspecified+no_connect"))
    )
    (net (code "116") (name "unconnected-(U6-n{slash}a-Pad4)") (class "Default")
      (node (ref "U6") (pin "4") (pinfunction "n/a_4") (pintype "unspecified+no_connect"))
    )
    (net (code "117") (name "unconnected-(U10-PC13-TAMPER-RTC-Pad2)") (class "Default")
      (node (ref "U10") (pin "2") (pinfunction "PC13-TAMPER-RTC_2") (pintype "unspecified+no_connect"))
    )
    (net (code "118") (name "unconnected-(U10-PD0-OSCIN-Pad5)") (class "Default")
      (node (ref "U10") (pin "5") (pinfunction "PD0-OSCIN_5") (pintype "unspecified+no_connect"))
    )
    (net (code "119") (name "unconnected-(U10-PD1-OSCOUT-Pad6)") (class "Default")
      (node (ref "U10") (pin "6") (pinfunction "PD1-OSCOUT_6") (pintype "unspecified+no_connect"))
    )
    (net (code "120") (name "unconnected-(U11-NC-Pad20)") (class "Default")
      (node (ref "U11") (pin "20") (pinfunction "NC_20") (pintype "input+no_connect"))
    )
    (net (code "121") (name "unconnected-(U11-P00-Pad6)") (class "Default")
      (node (ref "U11") (pin "6") (pinfunction "P00_6") (pintype "input+no_connect"))
    )
    (net (code "122") (name "unconnected-(U15-NC-Pad4)") (class "Default")
      (node (ref "U15") (pin "4") (pinfunction "NC_4") (pintype "unspecified+no_connect"))
    )
    (net (code "123") (name "unconnected-(USB1-SBUS1-PadA8)") (class "Default")
      (node (ref "USB1") (pin "A8") (pinfunction "SBUS1_A8") (pintype "input+no_connect"))
    )
    (net (code "124") (name "unconnected-(USB1-SBUS2-PadB8)") (class "Default")
      (node (ref "USB1") (pin "B8") (pinfunction "SBUS2_B8") (pintype "input+no_connect"))
    )
  )
)
